# USB_DataOnly.net
KiCad netlist of a schematic drawn in Altium Designer
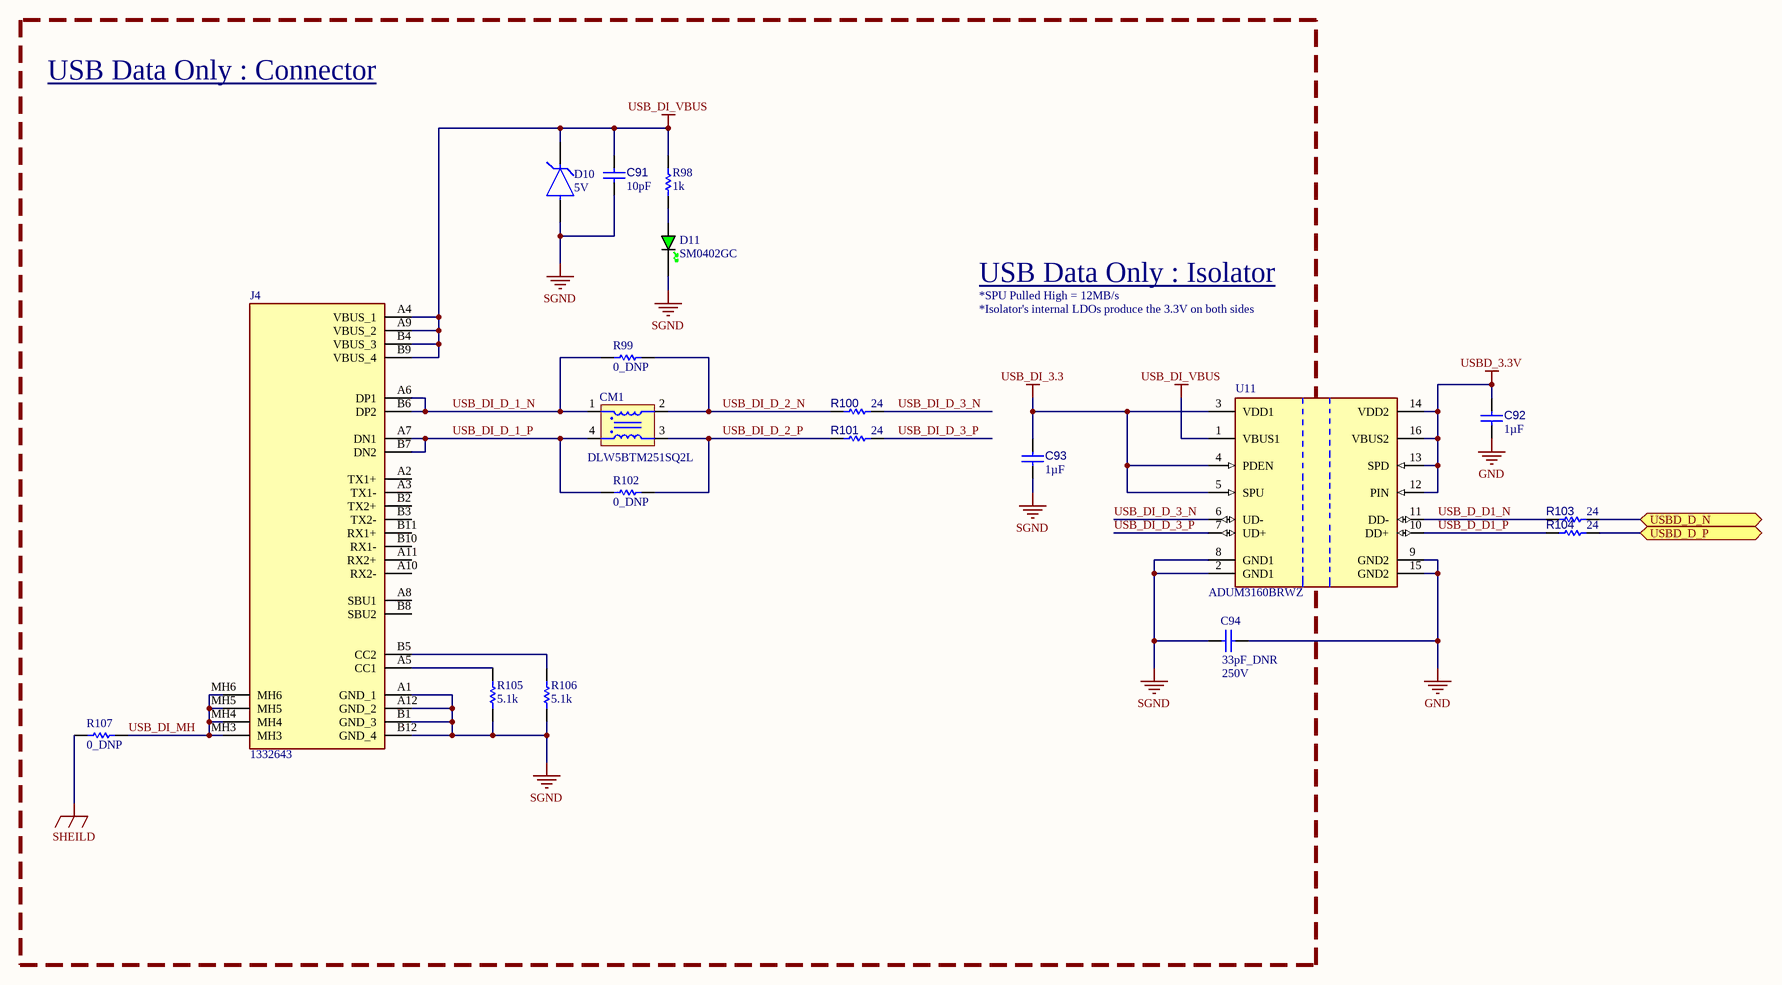
[diagram p0: USB_DataOnly.SchDoc]

(export (version "E")
  (design (tool "Eeschema 10.0.6"))
  (components
    (comp (ref "C91")
      (value "10pF")
      (footprint "CAPC1005X55X25ML05T05")
      (description "Chip Capacitor, 10 pF, +/- 5%, 50 V, 0402 (1005 Metric)")
      (fields (field (name "TOLERANCE") "5%") (field (name "Comment") "Capacitor 10 pF +/- 5% 50 V 0402"))
      (libsource (lib "Personal Workspace") (part "CAP-NP-2"))
    )
    (comp (ref "C92")
      (value "1µF")
      (footprint "CAPC2013X135X45NL10T25")
      (description "Chip Capacitor, 1 uF, +/- 10%, 50 V, 0805 (2012 Metric)")
      (fields (field (name "TOLERANCE") "10%") (field (name "Comment") "Capacitor 1 uF +/- 10% 50 V 0805"))
      (libsource (lib "Personal Workspace") (part "CAP-NP-2"))
    )
    (comp (ref "C93")
      (value "1µF")
      (footprint "CAPC2013X135X45NL10T25")
      (description "Chip Capacitor, 1 uF, +/- 10%, 50 V, 0805 (2012 Metric)")
      (fields (field (name "TOLERANCE") "10%") (field (name "Comment") "Capacitor 1 uF +/- 10% 50 V 0805"))
      (libsource (lib "Personal Workspace") (part "CAP-NP-2"))
    )
    (comp (ref "C94")
      (value "8853520100071")
      (footprint "WCAP-CSSA_1808_L4.5W2H1.4")
      (description "8853520100071 Suppression Cap, 33Pf, Class X1/Y2 Rohs Compliant: Yes")
      (fields (field (name "CAPACITANCE") "33pF_DNR") (field (name "VOLTAGE RATING") "250V"))
      (libsource (lib "Altium Content Vault") (part "Capacitor_Non-Polarized"))
    )
    (comp (ref "CM1")
      (value "DLW5BTM251SQ2L")
      (footprint "CMC-2020")
      (description "Common Mode Choke 5A 250R 20mR")
      (fields (field (name "MANUFACTURER") "Murata") (field (name "SOURCE") "Schematic-Lib-PhilsLab.SchLib"))
      (libsource (lib "Personal Workspace") (part "DLW5BTM251SQ2L"))
    )
    (comp (ref "D10")
      (value "SMAJ5.0A-13-F")
      (footprint "FP-SMA-MFG")
      (description "TVS DIODE 5V 9.2V SMA")
      (fields
        (field (name "MANUFACTURER") "Diodes Inc.")
        (field (name "OCTOPART") "https://octopart.com/smaj5.0a-13-f-diodes+inc.-350158")
        (field (name "REVERSE STANDOFF VOLTAGE") "5V")
      )
      (libsource (lib "Personal Workspace") (part "SMAJ5.0A-13-F"))
    )
    (comp (ref "D11")
      (value "SM0402GC")
      (footprint "FP-SM0402GC-MFG")
      (description "LED Uni-Color Green 575nm 2-PinChip 0402(1006Metric) T/R")
      (libsource (lib "Personal Workspace") (part "LED_0805_GREEN"))
    )
    (comp (ref "J4")
      (value "1332643")
      (footprint "1332643")
      (description "USB-C connector. Horizontal layout. 5A amp rated.")
      (fields (field (name "MOUSER PART NUMBER") "651-1332643"))
      (libsource (lib "Personal Workspace") (part "1332643"))
    )
    (comp (ref "R98")
      (value "1k")
      (footprint "RESC0402(1005)_L")
      (description "Chip Resistor, 1 kOhms, +/-5 %, 63 mW, -55 to 155 degC, 0402")
      (fields (field (name "TOLERANCE") "5%") (field (name "POWER") "63mW"))
      (libsource (lib "") (part "RES-2_1"))
    )
    (comp (ref "R99")
      (value "0_DNP")
      (footprint "RESC1005X40X25ML05T05")
      (description "Chip Resistor, 0 Ohm, +/- 5%, 63 mW, -55 to 155 degC, 0402 (1005 Metric)")
      (fields (field (name "POWER") "63mW") (field (name "TOLERANCE") "5%"))
      (libsource (lib "") (part "RES-2_1"))
    )
    (comp (ref "R100")
      (value "24")
      (footprint "FP-CR0402-IPC_C")
      (description "Res Thick Film 0402 24 Ohm 1% 0.063W(1/16W) ±100ppm/C Pad SMD T/R")
      (fields (field (name "TOLERANCE") "1%") (field (name "Comment") "CR0402-FX-24R0GLF"))
      (libsource (lib "Personal Workspace") (part "RES-2"))
    )
    (comp (ref "R101")
      (value "24")
      (footprint "FP-CR0402-IPC_C")
      (description "Res Thick Film 0402 24 Ohm 1% 0.063W(1/16W) ±100ppm/C Pad SMD T/R")
      (fields (field (name "TOLERANCE") "1%") (field (name "Comment") "CR0402-FX-24R0GLF"))
      (libsource (lib "Personal Workspace") (part "RES-2"))
    )
    (comp (ref "R102")
      (value "0_DNP")
      (footprint "RESC1005X40X25ML05T05")
      (description "Chip Resistor, 0 Ohm, +/- 5%, 63 mW, -55 to 155 degC, 0402 (1005 Metric)")
      (fields (field (name "POWER") "63mW") (field (name "TOLERANCE") "5%"))
      (libsource (lib "") (part "RES-2_1"))
    )
    (comp (ref "R103")
      (value "24")
      (footprint "FP-CR0402-IPC_C")
      (description "Res Thick Film 0402 24 Ohm 1% 0.063W(1/16W) ±100ppm/C Pad SMD T/R")
      (fields (field (name "TOLERANCE") "1%") (field (name "Comment") "CR0402-FX-24R0GLF"))
      (libsource (lib "Personal Workspace") (part "RES-2"))
    )
    (comp (ref "R104")
      (value "24")
      (footprint "FP-CR0402-IPC_C")
      (description "Res Thick Film 0402 24 Ohm 1% 0.063W(1/16W) ±100ppm/C Pad SMD T/R")
      (fields (field (name "TOLERANCE") "1%") (field (name "Comment") "CR0402-FX-24R0GLF"))
      (libsource (lib "Personal Workspace") (part "RES-2"))
    )
    (comp (ref "R105")
      (value "5.1k")
      (footprint "FP-RN73R1E-MFG")
      (description "Fixed Resistor, Thin Film, 0.1W, 5100ohm, 50V, 1% +/-Tol, 25ppm/Cel, Surface Mount, 0402")
      (fields (field (name "TOLERANCE") "1%") (field (name "Comment") "RN73R1ETTP5101F25"))
      (libsource (lib "") (part "RES-2_1"))
    )
    (comp (ref "R106")
      (value "5.1k")
      (footprint "FP-RN73R1E-MFG")
      (description "Fixed Resistor, Thin Film, 0.1W, 5100ohm, 50V, 1% +/-Tol, 25ppm/Cel, Surface Mount, 0402")
      (fields (field (name "TOLERANCE") "1%") (field (name "Comment") "RN73R1ETTP5101F25"))
      (libsource (lib "") (part "RES-2_1"))
    )
    (comp (ref "R107")
      (value "0_DNP")
      (footprint "RESC1005X40X25ML05T05")
      (description "Chip Resistor, 0 Ohm, +/- 5%, 63 mW, -55 to 155 degC, 0402 (1005 Metric)")
      (fields (field (name "POWER") "63mW") (field (name "TOLERANCE") "5%"))
      (libsource (lib "") (part "RES-2_1"))
    )
    (comp (ref "U11")
      (value "ADUM3160BRWZ")
      (footprint "FP-RW-16-IPC_C")
      (description "DGT ISOL 2500VRMS 2CH USB 16SOIC")
      (libsource (lib "Altium Content Vault") (part "e41304a63d8dc83c3ae01294c006d0e"))
    )
  )
  (nets
    (net (code "1") (name "/USBD_D_N") (class "Default")
      (node (ref "R103") (pin "2") (pinfunction "2_2") (pintype "passive"))
    )
    (net (code "2") (name "/USBD_D_P") (class "Default")
      (node (ref "R104") (pin "2") (pinfunction "2_2") (pintype "passive"))
    )
    (net (code "3") (name "/USB_DI_D_1_N") (class "Default")
      (node (ref "CM1") (pin "1") (pinfunction "1_1") (pintype "passive"))
      (node (ref "J4") (pin "A6") (pinfunction "DP1_A6") (pintype "passive"))
      (node (ref "J4") (pin "B6") (pinfunction "DP2_B6") (pintype "passive"))
      (node (ref "R99") (pin "1") (pinfunction "1_1") (pintype "passive"))
    )
    (net (code "4") (name "/USB_DI_D_1_P") (class "Default")
      (node (ref "CM1") (pin "4") (pinfunction "4_4") (pintype "passive"))
      (node (ref "J4") (pin "A7") (pinfunction "DN1_A7") (pintype "passive"))
      (node (ref "J4") (pin "B7") (pinfunction "DN2_B7") (pintype "passive"))
      (node (ref "R102") (pin "1") (pinfunction "1_1") (pintype "passive"))
    )
    (net (code "5") (name "/USB_DI_D_2_N") (class "Default")
      (node (ref "CM1") (pin "2") (pinfunction "2_2") (pintype "passive"))
      (node (ref "R100") (pin "1") (pinfunction "1_1") (pintype "passive"))
      (node (ref "R99") (pin "2") (pinfunction "2_2") (pintype "passive"))
    )
    (net (code "6") (name "/USB_DI_D_2_P") (class "Default")
      (node (ref "CM1") (pin "3") (pinfunction "3_3") (pintype "passive"))
      (node (ref "R101") (pin "1") (pinfunction "1_1") (pintype "passive"))
      (node (ref "R102") (pin "2") (pinfunction "2_2") (pintype "passive"))
    )
    (net (code "7") (name "/USB_DI_D_3_N") (class "Default")
      (node (ref "R100") (pin "2") (pinfunction "2_2") (pintype "passive"))
      (node (ref "U11") (pin "6") (pinfunction "UD-_6") (pintype "bidirectional"))
    )
    (net (code "8") (name "/USB_DI_D_3_P") (class "Default")
      (node (ref "R101") (pin "2") (pinfunction "2_2") (pintype "passive"))
      (node (ref "U11") (pin "7") (pinfunction "UD+_7") (pintype "bidirectional"))
    )
    (net (code "9") (name "/USB_DI_MH") (class "Default")
      (node (ref "J4") (pin "MH3") (pinfunction "MH3_MH3") (pintype "passive"))
      (node (ref "J4") (pin "MH4") (pinfunction "MH4_MH4") (pintype "passive"))
      (node (ref "J4") (pin "MH5") (pinfunction "MH5_MH5") (pintype "passive"))
      (node (ref "J4") (pin "MH6") (pinfunction "MH6_MH6") (pintype "passive"))
      (node (ref "R107") (pin "2") (pinfunction "2_2") (pintype "passive"))
    )
    (net (code "10") (name "/USB_D_D1_N") (class "Default")
      (node (ref "R103") (pin "1") (pinfunction "1_1") (pintype "passive"))
      (node (ref "U11") (pin "11") (pinfunction "DD-_11") (pintype "bidirectional"))
    )
    (net (code "11") (name "/USB_D_D1_P") (class "Default")
      (node (ref "R104") (pin "1") (pinfunction "1_1") (pintype "passive"))
      (node (ref "U11") (pin "10") (pinfunction "DD+_10") (pintype "bidirectional"))
    )
    (net (code "12") (name "GND") (class "Default")
      (node (ref "C92") (pin "1") (pinfunction "1_1") (pintype "passive"))
      (node (ref "C94") (pin "2") (pinfunction "2_2") (pintype "passive"))
      (node (ref "U11") (pin "15") (pinfunction "GND2_15") (pintype "power_in"))
      (node (ref "U11") (pin "9") (pinfunction "GND2_9") (pintype "power_in"))
    )
    (net (code "13") (name "Net-(D11-PadA)") (class "Default")
      (node (ref "D11") (pin "A") (pinfunction "A_A") (pintype "passive"))
      (node (ref "R98") (pin "1") (pinfunction "1_1") (pintype "passive"))
    )
    (net (code "14") (name "Net-(J4-CC1)") (class "Default")
      (node (ref "J4") (pin "A5") (pinfunction "CC1_A5") (pintype "passive"))
      (node (ref "R105") (pin "2") (pinfunction "2_2") (pintype "passive"))
    )
    (net (code "15") (name "Net-(J4-CC2)") (class "Default")
      (node (ref "J4") (pin "B5") (pinfunction "CC2_B5") (pintype "passive"))
      (node (ref "R106") (pin "2") (pinfunction "2_2") (pintype "passive"))
    )
    (net (code "16") (name "SGND") (class "Default")
      (node (ref "C91") (pin "1") (pinfunction "1_1") (pintype "passive"))
      (node (ref "C93") (pin "1") (pinfunction "1_1") (pintype "passive"))
      (node (ref "C94") (pin "1") (pinfunction "1_1") (pintype "passive"))
      (node (ref "D10") (pin "2") (pinfunction "A_2") (pintype "passive"))
      (node (ref "D11") (pin "K") (pinfunction "K_K") (pintype "passive"))
      (node (ref "J4") (pin "A1") (pinfunction "GND_1_A1") (pintype "passive"))
      (node (ref "J4") (pin "A12") (pinfunction "GND_2_A12") (pintype "passive"))
      (node (ref "J4") (pin "B1") (pinfunction "GND_3_B1") (pintype "passive"))
      (node (ref "J4") (pin "B12") (pinfunction "GND_4_B12") (pintype "passive"))
      (node (ref "R105") (pin "1") (pinfunction "1_1") (pintype "passive"))
      (node (ref "R106") (pin "1") (pinfunction "1_1") (pintype "passive"))
      (node (ref "U11") (pin "2") (pinfunction "GND1_2") (pintype "power_in"))
      (node (ref "U11") (pin "8") (pinfunction "GND1_8") (pintype "power_in"))
    )
    (net (code "17") (name "SHEILD") (class "Default")
      (node (ref "R107") (pin "1") (pinfunction "1_1") (pintype "passive"))
    )
    (net (code "18") (name "USBD_3.3V") (class "Default")
      (node (ref "C92") (pin "2") (pinfunction "2_2") (pintype "passive"))
      (node (ref "U11") (pin "12") (pinfunction "PIN_12") (pintype "input"))
      (node (ref "U11") (pin "13") (pinfunction "SPD_13") (pintype "input"))
      (node (ref "U11") (pin "14") (pinfunction "VDD2_14") (pintype "power_in"))
      (node (ref "U11") (pin "16") (pinfunction "VBUS2_16") (pintype "power_in"))
    )
    (net (code "19") (name "USB_DI_3.3") (class "Default")
      (node (ref "C93") (pin "2") (pinfunction "2_2") (pintype "passive"))
      (node (ref "U11") (pin "3") (pinfunction "VDD1_3") (pintype "power_in"))
      (node (ref "U11") (pin "4") (pinfunction "PDEN_4") (pintype "input"))
      (node (ref "U11") (pin "5") (pinfunction "SPU_5") (pintype "input"))
    )
    (net (code "20") (name "USB_DI_VBUS") (class "Default")
      (node (ref "C91") (pin "2") (pinfunction "2_2") (pintype "passive"))
      (node (ref "D10") (pin "1") (pinfunction "C_1") (pintype "passive"))
      (node (ref "J4") (pin "A4") (pinfunction "VBUS_1_A4") (pintype "passive"))
      (node (ref "J4") (pin "A9") (pinfunction "VBUS_2_A9") (pintype "passive"))
      (node (ref "J4") (pin "B4") (pinfunction "VBUS_3_B4") (pintype "passive"))
      (node (ref "J4") (pin "B9") (pinfunction "VBUS_4_B9") (pintype "passive"))
      (node (ref "R98") (pin "2") (pinfunction "2_2") (pintype "passive"))
      (node (ref "U11") (pin "1") (pinfunction "VBUS1_1") (pintype "power_in"))
    )
    (net (code "21") (name "unconnected-(J4-RX1+-PadB11)") (class "Default")
      (node (ref "J4") (pin "B11") (pinfunction "RX1+_B11") (pintype "passive"))
    )
    (net (code "22") (name "unconnected-(J4-RX1--PadB10)") (class "Default")
      (node (ref "J4") (pin "B10") (pinfunction "RX1-_B10") (pintype "passive"))
    )
    (net (code "23") (name "unconnected-(J4-RX2+-PadA11)") (class "Default")
      (node (ref "J4") (pin "A11") (pinfunction "RX2+_A11") (pintype "passive"))
    )
    (net (code "24") (name "unconnected-(J4-RX2--PadA10)") (class "Default")
      (node (ref "J4") (pin "A10") (pinfunction "RX2-_A10") (pintype "passive"))
    )
    (net (code "25") (name "unconnected-(J4-SBU1-PadA8)") (class "Default")
      (node (ref "J4") (pin "A8") (pinfunction "SBU1_A8") (pintype "passive"))
    )
    (net (code "26") (name "unconnected-(J4-SBU2-PadB8)") (class "Default")
      (node (ref "J4") (pin "B8") (pinfunction "SBU2_B8") (pintype "passive"))
    )
    (net (code "27") (name "unconnected-(J4-TX1+-PadA2)") (class "Default")
      (node (ref "J4") (pin "A2") (pinfunction "TX1+_A2") (pintype "passive"))
    )
    (net (code "28") (name "unconnected-(J4-TX1--PadA3)") (class "Default")
      (node (ref "J4") (pin "A3") (pinfunction "TX1-_A3") (pintype "passive"))
    )
    (net (code "29") (name "unconnected-(J4-TX2+-PadB2)") (class "Default")
      (node (ref "J4") (pin "B2") (pinfunction "TX2+_B2") (pintype "passive"))
    )
    (net (code "30") (name "unconnected-(J4-TX2--PadB3)") (class "Default")
      (node (ref "J4") (pin "B3") (pinfunction "TX2-_B3") (pintype "passive"))
    )
  )
)
